# Heaters.net
KiCad netlist of a schematic drawn in Altium Designer
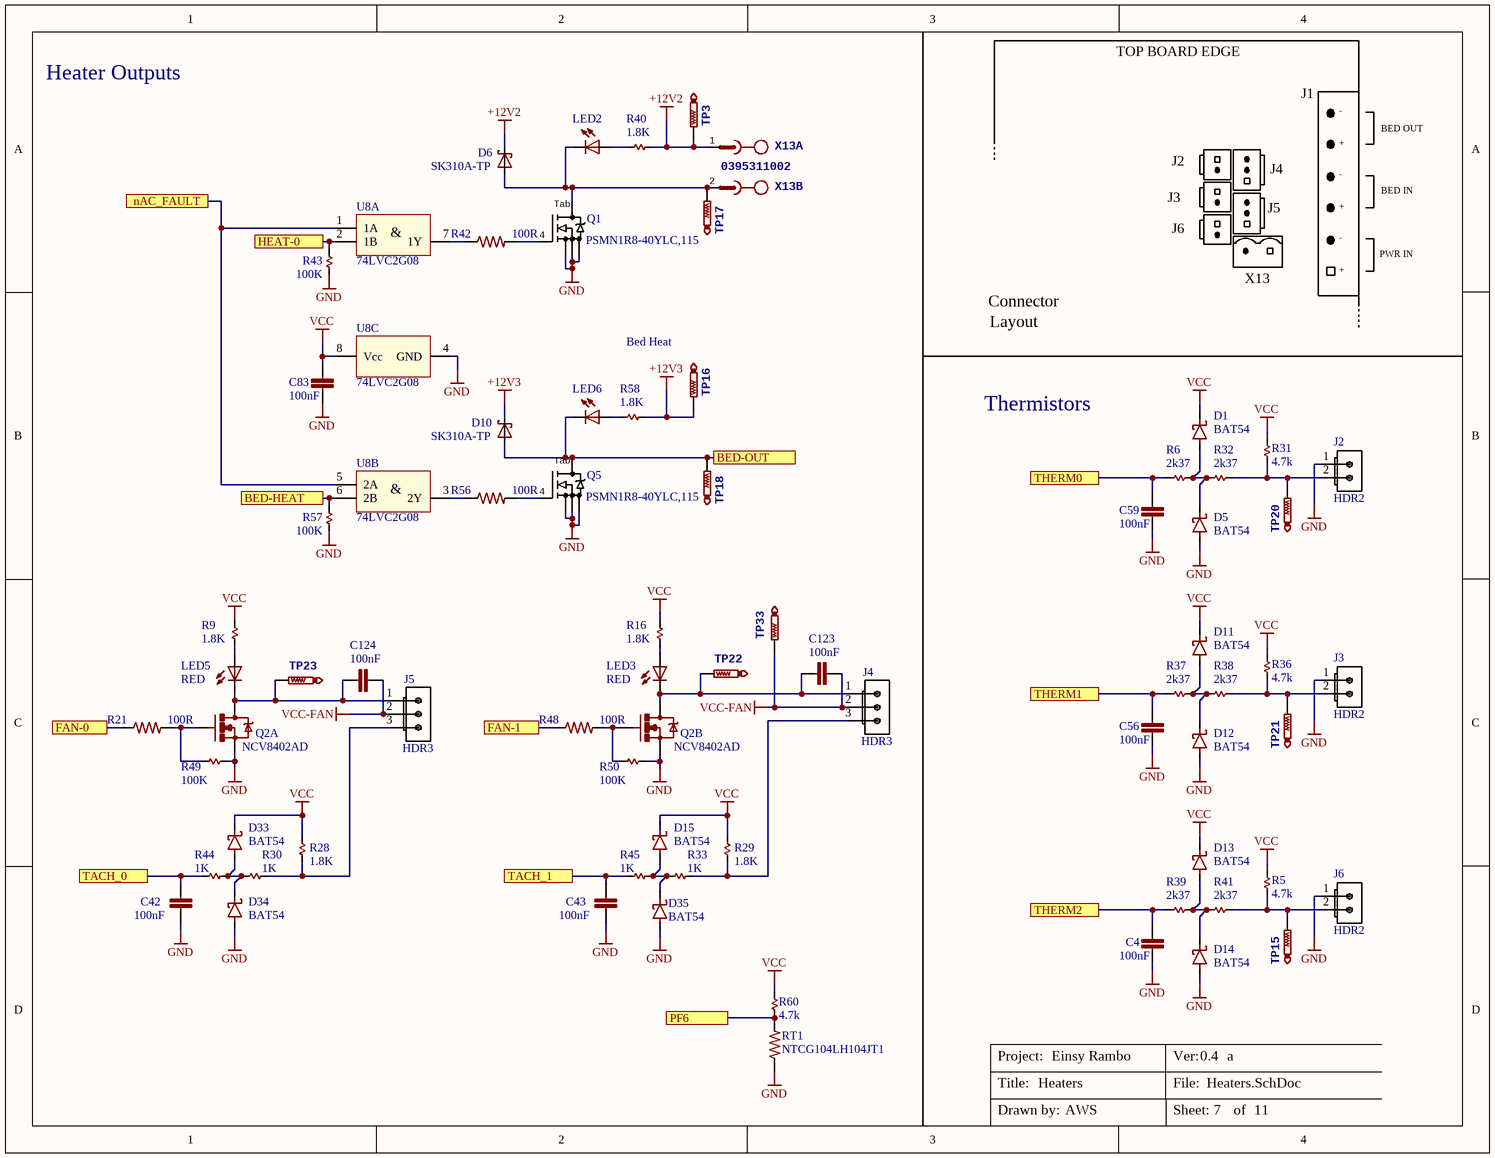
[diagram p0: Heaters.SchDoc]

(export (version "E")
  (design (tool "Eeschema 10.0.6"))
  (components
    (comp (ref "C4")
      (value "100nF")
      (footprint "C0402")
      (description "CAP CER 0402 100nF 16V 10% X7R")
      (fields (field (name "MANUFACTURER") "Murata") (field (name "TOLERANCE") "+/- 10%"))
      (libsource (lib "3Delight") (part "GRM155R71C104KA88D"))
    )
    (comp (ref "C42")
      (value "100nF")
      (footprint "C0402")
      (description "CAP CER 0402 100nF 16V 10% X7R")
      (fields (field (name "MANUFACTURER") "Murata") (field (name "TOLERANCE") "+/- 10%"))
      (libsource (lib "3Delight") (part "GRM155R71C104KA88D"))
    )
    (comp (ref "C43")
      (value "100nF")
      (footprint "C0402")
      (description "CAP CER 0402 100nF 16V 10% X7R")
      (fields (field (name "MANUFACTURER") "Murata") (field (name "TOLERANCE") "+/- 10%"))
      (libsource (lib "3Delight") (part "GRM155R71C104KA88D"))
    )
    (comp (ref "C56")
      (value "100nF")
      (footprint "C0402")
      (description "CAP CER 0402 100nF 16V 10% X7R")
      (fields (field (name "MANUFACTURER") "Murata") (field (name "TOLERANCE") "+/- 10%"))
      (libsource (lib "3Delight") (part "GRM155R71C104KA88D"))
    )
    (comp (ref "C59")
      (value "100nF")
      (footprint "C0402")
      (description "CAP CER 0402 100nF 16V 10% X7R")
      (fields (field (name "MANUFACTURER") "Murata") (field (name "TOLERANCE") "+/- 10%"))
      (libsource (lib "3Delight") (part "GRM155R71C104KA88D"))
    )
    (comp (ref "C83")
      (value "100nF")
      (footprint "C0402")
      (description "CAP CER 0402 100nF 16V 10% X7R")
      (fields (field (name "MANUFACTURER") "Murata") (field (name "TOLERANCE") "+/- 10%"))
      (libsource (lib "3Delight") (part "GRM155R71C104KA88D"))
    )
    (comp (ref "C123")
      (value "100nF")
      (footprint "C0402")
      (description "CAP CER 0402 100nF 16V 10% X7R")
      (fields (field (name "MANUFACTURER") "Murata") (field (name "TOLERANCE") "+/- 10%"))
      (libsource (lib "") (part "GRM155R71C104KA88D_1"))
    )
    (comp (ref "C124")
      (value "100nF")
      (footprint "C0402")
      (description "CAP CER 0402 100nF 16V 10% X7R")
      (fields (field (name "MANUFACTURER") "Murata") (field (name "TOLERANCE") "+/- 10%"))
      (libsource (lib "") (part "GRM155R71C104KA88D_1"))
    )
    (comp (ref "D1")
      (value "BAT54")
      (footprint "SOD523_IPC")
      (description "Diode Schottky 30V 100mA Surface Mount SOD-523")
      (fields (field (name "MANUFACTURER") "Diodes Incorporated") (field (name "TOLERANCE") "NA"))
      (libsource (lib "3Delight") (part "BAT54WT-7"))
    )
    (comp (ref "D5")
      (value "BAT54")
      (footprint "SOD523_IPC")
      (description "Diode Schottky 30V 100mA Surface Mount SOD-523")
      (fields (field (name "MANUFACTURER") "Diodes Incorporated") (field (name "TOLERANCE") "NA"))
      (libsource (lib "3Delight") (part "BAT54WT-7"))
    )
    (comp (ref "D6")
      (value "SK310A-TP")
      (footprint "SMA-SM")
      (description "DIODE Schottky 3A SMA")
      (fields (field (name "MANUFACTURER") "MCC") (field (name "PART") "SK310A"))
      (libsource (lib "3Delight") (part "SK310A"))
    )
    (comp (ref "D10")
      (value "SK310A-TP")
      (footprint "SMA-SM")
      (description "DIODE Schottky 3A SMA")
      (fields (field (name "MANUFACTURER") "MCC") (field (name "PART") "SK310A"))
      (libsource (lib "3Delight") (part "SK310A"))
    )
    (comp (ref "D11")
      (value "BAT54")
      (footprint "SOD523_IPC")
      (description "Diode Schottky 30V 100mA Surface Mount SOD-523")
      (fields (field (name "MANUFACTURER") "Diodes Incorporated") (field (name "TOLERANCE") "NA"))
      (libsource (lib "3Delight") (part "BAT54WT-7"))
    )
    (comp (ref "D12")
      (value "BAT54")
      (footprint "SOD523_IPC")
      (description "Diode Schottky 30V 100mA Surface Mount SOD-523")
      (fields (field (name "MANUFACTURER") "Diodes Incorporated") (field (name "TOLERANCE") "NA"))
      (libsource (lib "3Delight") (part "BAT54WT-7"))
    )
    (comp (ref "D13")
      (value "BAT54")
      (footprint "SOD523_IPC")
      (description "Diode Schottky 30V 100mA Surface Mount SOD-523")
      (fields (field (name "MANUFACTURER") "Diodes Incorporated") (field (name "TOLERANCE") "NA"))
      (libsource (lib "3Delight") (part "BAT54WT-7"))
    )
    (comp (ref "D14")
      (value "BAT54")
      (footprint "SOD523_IPC")
      (description "Diode Schottky 30V 100mA Surface Mount SOD-523")
      (fields (field (name "MANUFACTURER") "Diodes Incorporated") (field (name "TOLERANCE") "NA"))
      (libsource (lib "3Delight") (part "BAT54WT-7"))
    )
    (comp (ref "D15")
      (value "BAT54")
      (footprint "SOD523_IPC")
      (description "Diode Schottky 30V 100mA Surface Mount SOD-523")
      (fields (field (name "MANUFACTURER") "Diodes Incorporated") (field (name "TOLERANCE") "NA"))
      (libsource (lib "3Delight") (part "BAT54WT-7"))
    )
    (comp (ref "D33")
      (value "BAT54")
      (footprint "SOD523_IPC")
      (description "Diode Schottky 30V 100mA Surface Mount SOD-523")
      (fields (field (name "MANUFACTURER") "Diodes Incorporated") (field (name "TOLERANCE") "NA"))
      (libsource (lib "3Delight") (part "BAT54WT-7"))
    )
    (comp (ref "D34")
      (value "BAT54")
      (footprint "SOD523_IPC")
      (description "Diode Schottky 30V 100mA Surface Mount SOD-523")
      (fields (field (name "MANUFACTURER") "Diodes Incorporated") (field (name "TOLERANCE") "NA"))
      (libsource (lib "3Delight") (part "BAT54WT-7"))
    )
    (comp (ref "D35")
      (value "BAT54")
      (footprint "SOD523_IPC")
      (description "Diode Schottky 30V 100mA Surface Mount SOD-523")
      (fields (field (name "MANUFACTURER") "Diodes Incorporated") (field (name "TOLERANCE") "NA"))
      (libsource (lib "3Delight") (part "BAT54WT-7"))
    )
    (comp (ref "J2")
      (value "HDR2")
      (footprint "70543-02 PIN-IN-PASTE")
      (description "Connector 2pos")
      (fields (field (name "MANUFACTURER") "Molex") (field (name "PART") "2 Pin Conn"))
      (libsource (lib "Connectors") (part "CONN 2PIN VERT 0.1{dblquote} SHRD LOCKING PIN-IN-PASTE"))
    )
    (comp (ref "J3")
      (value "HDR2")
      (footprint "70543-02 PIN-IN-PASTE")
      (description "Connector 2pos")
      (fields (field (name "MANUFACTURER") "Molex") (field (name "PART") "2 Pin Conn"))
      (libsource (lib "Connectors") (part "CONN 2PIN VERT 0.1{dblquote} SHRD LOCKING PIN-IN-PASTE"))
    )
    (comp (ref "J4")
      (value "HDR3")
      (footprint "70543-03 PIN-IN-PASTE")
      (description "3 Positions Header, Shrouded Connector 0.100\" (2.54mm) Through Hole Gold")
      (fields (field (name "MANUFACTURER") "Molex") (field (name "PART") "3 Pin Conn VERT"))
      (libsource (lib "Connectors") (part "CONN 3POS VERT 0.1{dblquote} SHRD LOCKING PIN-IN-PASTE"))
    )
    (comp (ref "J5")
      (value "HDR3")
      (footprint "70543-03 PIN-IN-PASTE")
      (description "3 Positions Header, Shrouded Connector 0.100\" (2.54mm) Through Hole Gold")
      (fields (field (name "MANUFACTURER") "Molex") (field (name "PART") "3 Pin Conn VERT"))
      (libsource (lib "Connectors") (part "CONN 3POS VERT 0.1{dblquote} SHRD LOCKING PIN-IN-PASTE"))
    )
    (comp (ref "J6")
      (value "HDR2")
      (footprint "70543-02 PIN-IN-PASTE")
      (description "Connector 2pos")
      (fields (field (name "MANUFACTURER") "Molex") (field (name "PART") "2 Pin Conn"))
      (libsource (lib "Connectors") (part "CONN 2PIN VERT 0.1{dblquote} SHRD LOCKING PIN-IN-PASTE"))
    )
    (comp (ref "LED2")
      (value "RED")
      (footprint "LED2012120")
      (description "LED 0805 Red")
      (fields (field (name "MANUFACTURER") "Dialight") (field (name "TOLERANCE") "NA"))
      (libsource (lib "3Delight") (part "5988110107F"))
    )
    (comp (ref "LED3")
      (value "RED")
      (footprint "LED2012120")
      (description "LED 0805 Red")
      (fields
        (field (name "MANUFACTURER") "Dialight")
        (field (name "PART") "RED")
        (field (name "TOLERANCE") "NA")
      )
      (libsource (lib "3Delight") (part "5988110107F"))
    )
    (comp (ref "LED5")
      (value "RED")
      (footprint "LED2012120")
      (description "LED 0805 Red")
      (fields
        (field (name "MANUFACTURER") "Dialight")
        (field (name "PART") "RED")
        (field (name "TOLERANCE") "NA")
      )
      (libsource (lib "3Delight") (part "5988110107F"))
    )
    (comp (ref "LED6")
      (value "RED")
      (footprint "LED2012120")
      (description "LED 0805 Red")
      (fields (field (name "MANUFACTURER") "Dialight") (field (name "TOLERANCE") "NA"))
      (libsource (lib "3Delight") (part "5988110107F"))
    )
    (comp (ref "Q1")
      (value "PSMN1R8-40YLC,115")
      (footprint "SOT669_ClosedBotVias")
      (description "MOSFET N-CH 40V 100A LFPAK")
      (fields (field (name "MANUFACTURER") "Nexperia") (field (name "TOLERANCE") "-NA-"))
      (libsource (lib "Transistors") (part "PSMN1R8-40YLC_ClosedBotVias"))
    )
    (comp (ref "Q2")
      (value "NCV8402AD")
      (footprint "NCV8402AD-SOIC8")
      (description "IC DVR LOW SIDE 8-SOIC")
      (fields (field (name "MANUFACTURER") "On Semi") (field (name "PART") "NCV8402"))
      (libsource (lib "3Delight") (part "NCV8402AD"))
    )
    (comp (ref "Q5")
      (value "PSMN1R8-40YLC,115")
      (footprint "SOT669_ClosedBotVias")
      (description "MOSFET N-CH 40V 100A LFPAK")
      (fields (field (name "MANUFACTURER") "Nexperia") (field (name "TOLERANCE") "-NA-"))
      (libsource (lib "Transistors") (part "PSMN1R8-40YLC_ClosedBotVias"))
    )
    (comp (ref "R5")
      (value "4.7k")
      (footprint "R0402")
      (description "RES SMD 4.7K OHM 1% 1/16W 0402")
      (fields (field (name "MANUFACTURER") "Yageo") (field (name "TOLERANCE") "+/- 1%"))
      (libsource (lib "3Delight") (part "RC0402FR-074K7L"))
    )
    (comp (ref "R6")
      (value "2k37")
      (footprint "R0402")
      (description "RES SMD 2.37K OHM 1% 1/16W 0402")
      (fields (field (name "MANUFACTURER") "Yageo") (field (name "PART") "2.37k"))
      (libsource (lib "3Delight") (part "RC0402FR-072K37L"))
    )
    (comp (ref "R9")
      (value "1.8K")
      (footprint "R0402")
      (description "RES SMD 1.8K OHM 1% 1/16W 0402")
      (fields (field (name "MANUFACTURER") "Yageo") (field (name "PART") "1.8k"))
      (libsource (lib "3Delight") (part "RC0402FR-071K8L"))
    )
    (comp (ref "R16")
      (value "1.8K")
      (footprint "R0402")
      (description "RES SMD 1.8K OHM 1% 1/16W 0402")
      (fields (field (name "MANUFACTURER") "Yageo") (field (name "PART") "1.8k"))
      (libsource (lib "3Delight") (part "RC0402FR-071K8L"))
    )
    (comp (ref "R21")
      (value "100R")
      (footprint "R0402")
      (description "RES SMD 100 OHM 1% 1/16W 0402")
      (fields (field (name "MANUFACTURER") "Yageo") (field (name "PART") "100R 1% 0402"))
      (libsource (lib "Archim") (part "RES 100R 0402 1%"))
    )
    (comp (ref "R28")
      (value "1.8K")
      (footprint "R0402")
      (description "RES SMD 1.8K OHM 1% 1/16W 0402")
      (fields (field (name "MANUFACTURER") "Yageo") (field (name "PART") "1.8k"))
      (libsource (lib "3Delight") (part "RC0402FR-071K8L"))
    )
    (comp (ref "R29")
      (value "1.8K")
      (footprint "R0402")
      (description "RES SMD 1.8K OHM 1% 1/16W 0402")
      (fields (field (name "MANUFACTURER") "Yageo") (field (name "PART") "1.8k"))
      (libsource (lib "3Delight") (part "RC0402FR-071K8L"))
    )
    (comp (ref "R30")
      (value "1K")
      (footprint "R0402")
      (description "RES SMD 1K OHM 1% 1/16W 0402")
      (fields (field (name "MANUFACTURER") "Yageo") (field (name "PART") "1k"))
      (libsource (lib "3Delight") (part "RC0402FR-071KL"))
    )
    (comp (ref "R31")
      (value "4.7k")
      (footprint "R0402")
      (description "RES SMD 4.7K OHM 1% 1/16W 0402")
      (fields (field (name "MANUFACTURER") "Yageo") (field (name "TOLERANCE") "+/- 1%"))
      (libsource (lib "3Delight") (part "RC0402FR-074K7L"))
    )
    (comp (ref "R32")
      (value "2k37")
      (footprint "R0402")
      (description "RES SMD 2.37K OHM 1% 1/16W 0402")
      (fields (field (name "MANUFACTURER") "Yageo") (field (name "PART") "2.37k"))
      (libsource (lib "3Delight") (part "RC0402FR-072K37L"))
    )
    (comp (ref "R33")
      (value "1K")
      (footprint "R0402")
      (description "RES SMD 1K OHM 1% 1/16W 0402")
      (fields (field (name "MANUFACTURER") "Yageo") (field (name "PART") "1k"))
      (libsource (lib "3Delight") (part "RC0402FR-071KL"))
    )
    (comp (ref "R36")
      (value "4.7k")
      (footprint "R0402")
      (description "RES SMD 4.7K OHM 1% 1/16W 0402")
      (fields (field (name "MANUFACTURER") "Yageo") (field (name "TOLERANCE") "+/- 1%"))
      (libsource (lib "3Delight") (part "RC0402FR-074K7L"))
    )
    (comp (ref "R37")
      (value "2k37")
      (footprint "R0402")
      (description "RES SMD 2.37K OHM 1% 1/16W 0402")
      (fields (field (name "MANUFACTURER") "Yageo") (field (name "PART") "2.37k"))
      (libsource (lib "3Delight") (part "RC0402FR-072K37L"))
    )
    (comp (ref "R38")
      (value "2k37")
      (footprint "R0402")
      (description "RES SMD 2.37K OHM 1% 1/16W 0402")
      (fields (field (name "MANUFACTURER") "Yageo") (field (name "PART") "2.37k"))
      (libsource (lib "3Delight") (part "RC0402FR-072K37L"))
    )
    (comp (ref "R39")
      (value "2k37")
      (footprint "R0402")
      (description "RES SMD 2.37K OHM 1% 1/16W 0402")
      (fields (field (name "MANUFACTURER") "Yageo") (field (name "PART") "2.37k"))
      (libsource (lib "3Delight") (part "RC0402FR-072K37L"))
    )
    (comp (ref "R40")
      (value "1.8K")
      (footprint "R0402")
      (description "RES SMD 1.8K OHM 1% 1/16W 0402")
      (fields (field (name "MANUFACTURER") "Yageo") (field (name "PART") "1.8k"))
      (libsource (lib "3Delight") (part "RC0402FR-071K8L"))
    )
    (comp (ref "R41")
      (value "2k37")
      (footprint "R0402")
      (description "RES SMD 2.37K OHM 1% 1/16W 0402")
      (fields (field (name "MANUFACTURER") "Yageo") (field (name "PART") "2.37k"))
      (libsource (lib "3Delight") (part "RC0402FR-072K37L"))
    )
    (comp (ref "R42")
      (value "100R")
      (footprint "R0402")
      (description "RES SMD 100 OHM 1% 1/16W 0402")
      (fields (field (name "MANUFACTURER") "Yageo") (field (name "PART") "100R 1% 0402"))
      (libsource (lib "Archim") (part "RES 100R 0402 1%"))
    )
    (comp (ref "R43")
      (value "100K")
      (footprint "R0402")
      (description "RES 100K OHM 1% 1/16W 0402")
      (fields (field (name "MANUFACTURER") "Yageo") (field (name "TOLERANCE") "+/- 1%"))
      (libsource (lib "3Delight") (part "RC0402FR-07100KL"))
    )
    (comp (ref "R44")
      (value "1K")
      (footprint "R0402")
      (description "RES SMD 1K OHM 1% 1/16W 0402")
      (fields (field (name "MANUFACTURER") "Yageo") (field (name "PART") "1k"))
      (libsource (lib "3Delight") (part "RC0402FR-071KL"))
    )
    (comp (ref "R45")
      (value "1K")
      (footprint "R0402")
      (description "RES SMD 1K OHM 1% 1/16W 0402")
      (fields (field (name "MANUFACTURER") "Yageo") (field (name "PART") "1k"))
      (libsource (lib "3Delight") (part "RC0402FR-071KL"))
    )
    (comp (ref "R48")
      (value "100R")
      (footprint "R0402")
      (description "RES SMD 100 OHM 1% 1/16W 0402")
      (fields (field (name "MANUFACTURER") "Yageo") (field (name "PART") "100R 1% 0402"))
      (libsource (lib "Archim") (part "RES 100R 0402 1%"))
    )
    (comp (ref "R49")
      (value "100K")
      (footprint "R0402")
      (description "RES 100K OHM 1% 1/16W 0402")
      (fields (field (name "MANUFACTURER") "Yageo") (field (name "TOLERANCE") "+/- 1%"))
      (libsource (lib "3Delight") (part "RC0402FR-07100KL"))
    )
    (comp (ref "R50")
      (value "100K")
      (footprint "R0402")
      (description "RES 100K OHM 1% 1/16W 0402")
      (fields (field (name "MANUFACTURER") "Yageo") (field (name "TOLERANCE") "+/- 1%"))
      (libsource (lib "3Delight") (part "RC0402FR-07100KL"))
    )
    (comp (ref "R56")
      (value "100R")
      (footprint "R0402")
      (description "RES SMD 100 OHM 1% 1/16W 0402")
      (fields (field (name "MANUFACTURER") "Yageo") (field (name "PART") "100R 1% 0402"))
      (libsource (lib "Archim") (part "RES 100R 0402 1%"))
    )
    (comp (ref "R57")
      (value "100K")
      (footprint "R0402")
      (description "RES 100K OHM 1% 1/16W 0402")
      (fields (field (name "MANUFACTURER") "Yageo") (field (name "TOLERANCE") "+/- 1%"))
      (libsource (lib "3Delight") (part "RC0402FR-07100KL"))
    )
    (comp (ref "R58")
      (value "1.8K")
      (footprint "R0402")
      (description "RES SMD 1.8K OHM 1% 1/16W 0402")
      (fields (field (name "MANUFACTURER") "Yageo") (field (name "PART") "1.8k"))
      (libsource (lib "3Delight") (part "RC0402FR-071K8L"))
    )
    (comp (ref "R60")
      (value "4.7k")
      (footprint "R0402")
      (description "RES SMD 4.7K OHM 1% 1/16W 0402")
      (fields (field (name "MANUFACTURER") "Yageo") (field (name "TOLERANCE") "+/- 1%"))
      (libsource (lib "3Delight") (part "RC0402FR-074K7L"))
    )
    (comp (ref "RT1")
      (value "NTCG104LH104JT1")
      (footprint "R0402")
      (description "Resistor")
      (fields (field (name "PUBLISHER") "UltiMachine"))
      (libsource (lib "3Delight") (part "R0402TBD"))
    )
    (comp (ref "TP3")
      (value "TestPoint")
      (footprint "TP1-27")
      (description "Test Point")
      (libsource (lib "") (part "TestPoint_2"))
    )
    (comp (ref "TP15")
      (value "TestPoint")
      (footprint "TP1-27")
      (description "Test Point")
      (libsource (lib "") (part "TestPoint_1"))
    )
    (comp (ref "TP16")
      (value "TestPoint")
      (footprint "TP1-27")
      (description "Test Point")
      (libsource (lib "") (part "TestPoint_2"))
    )
    (comp (ref "TP17")
      (value "TestPoint")
      (footprint "TP1-27")
      (description "Test Point")
      (libsource (lib "") (part "TestPoint_1"))
    )
    (comp (ref "TP18")
      (value "TestPoint")
      (footprint "TP1-27")
      (description "Test Point")
      (libsource (lib "") (part "TestPoint_1"))
    )
    (comp (ref "TP20")
      (value "TestPoint")
      (footprint "TP1-27")
      (description "Test Point")
      (libsource (lib "") (part "TestPoint_1"))
    )
    (comp (ref "TP21")
      (value "TestPoint")
      (footprint "TP1-27")
      (description "Test Point")
      (libsource (lib "") (part "TestPoint_1"))
    )
    (comp (ref "TP22")
      (value "TestPoint")
      (footprint "TP1-27")
      (description "Test Point")
      (libsource (lib "3Delight") (part "TestPoint"))
    )
    (comp (ref "TP23")
      (value "TestPoint")
      (footprint "TP1-27")
      (description "Test Point")
      (libsource (lib "3Delight") (part "TestPoint"))
    )
    (comp (ref "TP33")
      (value "TestPoint")
      (footprint "TP1-27")
      (description "Test Point")
      (libsource (lib "") (part "TestPoint_2"))
    )
    (comp (ref "U8")
      (value "74LVC2G08")
      (footprint "VSSOP8")
      (description "IC GATE AND 2CH 2-INP 8-VSSOP")
      (fields (field (name "TOLERANCE") "-NA-") (field (name "MANUFACTURER") "Nexperia"))
      (libsource (lib "ICs-Logic") (part "74LVC2G08"))
    )
    (comp (ref "X13")
      (value "0395311002")
      (footprint "MSTBV2")
      (description "Conn - 5.08mm Pitch Fixed")
      (fields (field (name "MANUFACTURER") "Molex") (field (name "PART") "2POS"))
      (libsource (lib "") (part "0395311002_1"))
    )
  )
  (nets
    (net (code "1") (name "+12V2") (class "Default")
      (node (ref "D6") (pin "C") (pinfunction "C_C") (pintype "passive"))
      (node (ref "R40") (pin "1") (pinfunction "1_1") (pintype "passive"))
      (node (ref "TP3") (pin "TP") (pinfunction "TP_TP") (pintype "passive"))
      (node (ref "X13") (pin "1") (pinfunction "1_1") (pintype "passive"))
    )
    (net (code "2") (name "+12V3") (class "Default")
      (node (ref "D10") (pin "C") (pinfunction "C_C") (pintype "passive"))
      (node (ref "R58") (pin "1") (pinfunction "1_1") (pintype "passive"))
      (node (ref "TP16") (pin "TP") (pinfunction "TP_TP") (pintype "passive"))
    )
    (net (code "3") (name "/BED-HEAT") (class "Default")
      (node (ref "R57") (pin "2") (pinfunction "2_2") (pintype "passive"))
      (node (ref "U8") (pin "6") (pinfunction "2B_6") (pintype "passive"))
    )
    (net (code "4") (name "/BED-OUT") (class "Default")
      (node (ref "D10") (pin "A") (pinfunction "A_A") (pintype "passive"))
      (node (ref "LED6") (pin "C") (pinfunction "C_C") (pintype "passive"))
      (node (ref "Q5") (pin "TAB") (pinfunction "D_TAB") (pintype "passive"))
      (node (ref "TP18") (pin "TP") (pinfunction "TP_TP") (pintype "passive"))
    )
    (net (code "5") (name "/FAN-0") (class "Default")
      (node (ref "R21") (pin "1") (pinfunction "1_1") (pintype "passive"))
    )
    (net (code "6") (name "/FAN-1") (class "Default")
      (node (ref "R48") (pin "1") (pinfunction "1_1") (pintype "passive"))
    )
    (net (code "7") (name "/HEAT-0") (class "Default")
      (node (ref "R43") (pin "2") (pinfunction "2_2") (pintype "passive"))
      (node (ref "U8") (pin "2") (pinfunction "1B_2") (pintype "passive"))
    )
    (net (code "8") (name "/PF6") (class "Default")
      (node (ref "R60") (pin "1") (pinfunction "1_1") (pintype "passive"))
      (node (ref "RT1") (pin "2") (pinfunction "2_2") (pintype "passive"))
    )
    (net (code "9") (name "/TACH_0") (class "Default")
      (node (ref "C42") (pin "1") (pinfunction "1_1") (pintype "passive"))
      (node (ref "R44") (pin "1") (pinfunction "1_1") (pintype "passive"))
    )
    (net (code "10") (name "/TACH_1") (class "Default")
      (node (ref "C43") (pin "1") (pinfunction "1_1") (pintype "passive"))
      (node (ref "R45") (pin "1") (pinfunction "1_1") (pintype "passive"))
    )
    (net (code "11") (name "/THERM0") (class "Default")
      (node (ref "C59") (pin "1") (pinfunction "1_1") (pintype "passive"))
      (node (ref "R6") (pin "2") (pinfunction "2_2") (pintype "passive"))
    )
    (net (code "12") (name "/THERM1") (class "Default")
      (node (ref "C56") (pin "1") (pinfunction "1_1") (pintype "passive"))
      (node (ref "R37") (pin "2") (pinfunction "2_2") (pintype "passive"))
    )
    (net (code "13") (name "/THERM2") (class "Default")
      (node (ref "C4") (pin "1") (pinfunction "1_1") (pintype "passive"))
      (node (ref "R39") (pin "2") (pinfunction "2_2") (pintype "passive"))
    )
    (net (code "14") (name "/nAC_FAULT") (class "Default")
      (node (ref "U8") (pin "1") (pinfunction "1A_1") (pintype "passive"))
      (node (ref "U8") (pin "5") (pinfunction "2A_5") (pintype "passive"))
    )
    (net (code "15") (name "GND") (class "Default")
      (node (ref "C4") (pin "2") (pinfunction "2_2") (pintype "passive"))
      (node (ref "C42") (pin "2") (pinfunction "2_2") (pintype "passive"))
      (node (ref "C43") (pin "2") (pinfunction "2_2") (pintype "passive"))
      (node (ref "C56") (pin "2") (pinfunction "2_2") (pintype "passive"))
      (node (ref "C59") (pin "2") (pinfunction "2_2") (pintype "passive"))
      (node (ref "C83") (pin "2") (pinfunction "2_2") (pintype "passive"))
      (node (ref "D12") (pin "A") (pinfunction "A_A") (pintype "passive"))
      (node (ref "D14") (pin "A") (pinfunction "A_A") (pintype "passive"))
      (node (ref "D34") (pin "A") (pinfunction "A_A") (pintype "passive"))
      (node (ref "D35") (pin "A") (pinfunction "A_A") (pintype "passive"))
      (node (ref "D5") (pin "A") (pinfunction "A_A") (pintype "passive"))
      (node (ref "J2") (pin "1") (pinfunction "S_1") (pintype "passive"))
      (node (ref "J3") (pin "1") (pinfunction "S_1") (pintype "passive"))
      (node (ref "J6") (pin "1") (pinfunction "S_1") (pintype "passive"))
      (node (ref "Q1") (pin "1") (pinfunction "S_1") (pintype "passive"))
      (node (ref "Q1") (pin "2") (pinfunction "S_2") (pintype "passive"))
      (node (ref "Q1") (pin "3") (pinfunction "S_3") (pintype "passive"))
      (node (ref "Q2") (pin "1") (pinfunction "S_1") (pintype "passive"))
      (node (ref "Q2") (pin "3") (pinfunction "S_3") (pintype "passive"))
      (node (ref "Q5") (pin "1") (pinfunction "S_1") (pintype "passive"))
      (node (ref "Q5") (pin "2") (pinfunction "S_2") (pintype "passive"))
      (node (ref "Q5") (pin "3") (pinfunction "S_3") (pintype "passive"))
      (node (ref "R43") (pin "1") (pinfunction "1_1") (pintype "passive"))
      (node (ref "R49") (pin "2") (pinfunction "2_2") (pintype "passive"))
      (node (ref "R50") (pin "2") (pinfunction "2_2") (pintype "passive"))
      (node (ref "R57") (pin "1") (pinfunction "1_1") (pintype "passive"))
      (node (ref "RT1") (pin "1") (pinfunction "1_1") (pintype "passive"))
      (node (ref "U8") (pin "4") (pinfunction "GND_4") (pintype "passive"))
    )
    (net (code "16") (name "Net-(D1-PadA)") (class "Default")
      (node (ref "D1") (pin "A") (pinfunction "A_A") (pintype "passive"))
      (node (ref "D5") (pin "K") (pinfunction "K_K") (pintype "passive"))
      (node (ref "R32") (pin "2") (pinfunction "2_2") (pintype "passive"))
      (node (ref "R6") (pin "1") (pinfunction "1_1") (pintype "passive"))
    )
    (net (code "17") (name "Net-(D11-PadA)") (class "Default")
      (node (ref "D11") (pin "A") (pinfunction "A_A") (pintype "passive"))
      (node (ref "D12") (pin "K") (pinfunction "K_K") (pintype "passive"))
      (node (ref "R37") (pin "1") (pinfunction "1_1") (pintype "passive"))
      (node (ref "R38") (pin "2") (pinfunction "2_2") (pintype "passive"))
    )
    (net (code "18") (name "Net-(D13-PadA)") (class "Default")
      (node (ref "D13") (pin "A") (pinfunction "A_A") (pintype "passive"))
      (node (ref "D14") (pin "K") (pinfunction "K_K") (pintype "passive"))
      (node (ref "R39") (pin "1") (pinfunction "1_1") (pintype "passive"))
      (node (ref "R41") (pin "2") (pinfunction "2_2") (pintype "passive"))
    )
    (net (code "19") (name "Net-(D15-PadA)") (class "Default")
      (node (ref "D15") (pin "A") (pinfunction "A_A") (pintype "passive"))
      (node (ref "D35") (pin "K") (pinfunction "K_K") (pintype "passive"))
      (node (ref "R33") (pin "1") (pinfunction "1_1") (pintype "passive"))
      (node (ref "R45") (pin "2") (pinfunction "2_2") (pintype "passive"))
    )
    (net (code "20") (name "Net-(D33-PadA)") (class "Default")
      (node (ref "D33") (pin "A") (pinfunction "A_A") (pintype "passive"))
      (node (ref "D34") (pin "K") (pinfunction "K_K") (pintype "passive"))
      (node (ref "R30") (pin "1") (pinfunction "1_1") (pintype "passive"))
      (node (ref "R44") (pin "2") (pinfunction "2_2") (pintype "passive"))
    )
    (net (code "21") (name "Net-(J2-S-Pad2)") (class "Default")
      (node (ref "J2") (pin "2") (pinfunction "S_2") (pintype "passive"))
      (node (ref "R31") (pin "1") (pinfunction "1_1") (pintype "passive"))
      (node (ref "R32") (pin "1") (pinfunction "1_1") (pintype "passive"))
      (node (ref "TP20") (pin "TP") (pinfunction "TP_TP") (pintype "passive"))
    )
    (net (code "22") (name "Net-(J3-S-Pad2)") (class "Default")
      (node (ref "J3") (pin "2") (pinfunction "S_2") (pintype "passive"))
      (node (ref "R36") (pin "1") (pinfunction "1_1") (pintype "passive"))
      (node (ref "R38") (pin "1") (pinfunction "1_1") (pintype "passive"))
      (node (ref "TP21") (pin "TP") (pinfunction "TP_TP") (pintype "passive"))
    )
    (net (code "23") (name "Net-(J4-S-Pad3)") (class "Default")
      (node (ref "J4") (pin "3") (pinfunction "S_3") (pintype "passive"))
      (node (ref "R29") (pin "1") (pinfunction "1_1") (pintype "passive"))
      (node (ref "R33") (pin "2") (pinfunction "2_2") (pintype "passive"))
    )
    (net (code "24") (name "Net-(J5-S-Pad3)") (class "Default")
      (node (ref "J5") (pin "3") (pinfunction "S_3") (pintype "passive"))
      (node (ref "R28") (pin "1") (pinfunction "1_1") (pintype "passive"))
      (node (ref "R30") (pin "2") (pinfunction "2_2") (pintype "passive"))
    )
    (net (code "25") (name "Net-(J6-S-Pad2)") (class "Default")
      (node (ref "J6") (pin "2") (pinfunction "S_2") (pintype "passive"))
      (node (ref "R41") (pin "1") (pinfunction "1_1") (pintype "passive"))
      (node (ref "R5") (pin "1") (pinfunction "1_1") (pintype "passive"))
      (node (ref "TP15") (pin "TP") (pinfunction "TP_TP") (pintype "passive"))
    )
    (net (code "26") (name "Net-(LED2-PadA)") (class "Default")
      (node (ref "LED2") (pin "A") (pinfunction "A_A") (pintype "passive"))
      (node (ref "R40") (pin "2") (pinfunction "2_2") (pintype "passive"))
    )
    (net (code "27") (name "Net-(LED3-PadA)") (class "Default")
      (node (ref "LED3") (pin "A") (pinfunction "A_A") (pintype "passive"))
      (node (ref "R16") (pin "2") (pinfunction "2_2") (pintype "passive"))
    )
    (net (code "28") (name "Net-(LED5-PadA)") (class "Default")
      (node (ref "LED5") (pin "A") (pinfunction "A_A") (pintype "passive"))
      (node (ref "R9") (pin "2") (pinfunction "2_2") (pintype "passive"))
    )
    (net (code "29") (name "Net-(LED6-PadA)") (class "Default")
      (node (ref "LED6") (pin "A") (pinfunction "A_A") (pintype "passive"))
      (node (ref "R58") (pin "2") (pinfunction "2_2") (pintype "passive"))
    )
    (net (code "30") (name "Net-(Q1-D)") (class "Default")
      (node (ref "D6") (pin "A") (pinfunction "A_A") (pintype "passive"))
      (node (ref "LED2") (pin "C") (pinfunction "C_C") (pintype "passive"))
      (node (ref "Q1") (pin "TAB") (pinfunction "D_TAB") (pintype "passive"))
      (node (ref "TP17") (pin "TP") (pinfunction "TP_TP") (pintype "passive"))
      (node (ref "X13") (pin "2") (pinfunction "1_2") (pintype "passive"))
    )
    (net (code "31") (name "Net-(Q1-G)") (class "Default")
      (node (ref "Q1") (pin "4") (pinfunction "G_4") (pintype "passive"))
      (node (ref "R42") (pin "2") (pinfunction "2_2") (pintype "passive"))
    )
    (net (code "32") (name "Net-(Q2A-D)") (class "Default")
      (node (ref "C124") (pin "1") (pinfunction "1_1") (pintype "passive"))
      (node (ref "J5") (pin "1") (pinfunction "S_1") (pintype "passive"))
      (node (ref "LED5") (pin "C") (pinfunction "C_C") (pintype "passive"))
      (node (ref "Q2") (pin "7") (pinfunction "D_7") (pintype "passive"))
      (node (ref "TP23") (pin "TP") (pinfunction "TP_TP") (pintype "passive"))
    )
    (net (code "33") (name "Net-(Q2A-G)") (class "Default")
      (node (ref "Q2") (pin "2") (pinfunction "G_2") (pintype "passive"))
      (node (ref "R21") (pin "2") (pinfunction "2_2") (pintype "passive"))
      (node (ref "R49") (pin "1") (pinfunction "1_1") (pintype "passive"))
    )
    (net (code "34") (name "Net-(Q2B-D)") (class "Default")
      (node (ref "C123") (pin "1") (pinfunction "1_1") (pintype "passive"))
      (node (ref "J4") (pin "1") (pinfunction "S_1") (pintype "passive"))
      (node (ref "LED3") (pin "C") (pinfunction "C_C") (pintype "passive"))
      (node (ref "Q2") (pin "5") (pinfunction "D_5") (pintype "passive"))
      (node (ref "TP22") (pin "TP") (pinfunction "TP_TP") (pintype "passive"))
    )
    (net (code "35") (name "Net-(Q2B-G)") (class "Default")
      (node (ref "Q2") (pin "4") (pinfunction "G_4") (pintype "passive"))
      (node (ref "R48") (pin "2") (pinfunction "2_2") (pintype "passive"))
      (node (ref "R50") (pin "1") (pinfunction "1_1") (pintype "passive"))
    )
    (net (code "36") (name "Net-(Q5-G)") (class "Default")
      (node (ref "Q5") (pin "4") (pinfunction "G_4") (pintype "passive"))
      (node (ref "R56") (pin "2") (pinfunction "2_2") (pintype "passive"))
    )
    (net (code "37") (name "Net-(U8A-1Y)") (class "Default")
      (node (ref "R42") (pin "1") (pinfunction "1_1") (pintype "passive"))
      (node (ref "U8") (pin "7") (pinfunction "1Y_7") (pintype "passive"))
    )
    (net (code "38") (name "Net-(U8B-2Y)") (class "Default")
      (node (ref "R56") (pin "1") (pinfunction "1_1") (pintype "passive"))
      (node (ref "U8") (pin "3") (pinfunction "2Y_3") (pintype "passive"))
    )
    (net (code "39") (name "VCC") (class "Default")
      (node (ref "C83") (pin "1") (pinfunction "1_1") (pintype "passive"))
      (node (ref "D1") (pin "K") (pinfunction "K_K") (pintype "passive"))
      (node (ref "D11") (pin "K") (pinfunction "K_K") (pintype "passive"))
      (node (ref "D13") (pin "K") (pinfunction "K_K") (pintype "passive"))
      (node (ref "D15") (pin "K") (pinfunction "K_K") (pintype "passive"))
      (node (ref "D33") (pin "K") (pinfunction "K_K") (pintype "passive"))
      (node (ref "R16") (pin "1") (pinfunction "1_1") (pintype "passive"))
      (node (ref "R28") (pin "2") (pinfunction "2_2") (pintype "passive"))
      (node (ref "R29") (pin "2") (pinfunction "2_2") (pintype "passive"))
      (node (ref "R31") (pin "2") (pinfunction "2_2") (pintype "passive"))
      (node (ref "R36") (pin "2") (pinfunction "2_2") (pintype "passive"))
      (node (ref "R5") (pin "2") (pinfunction "2_2") (pintype "passive"))
      (node (ref "R60") (pin "2") (pinfunction "2_2") (pintype "passive"))
      (node (ref "R9") (pin "1") (pinfunction "1_1") (pintype "passive"))
      (node (ref "U8") (pin "8") (pinfunction "Vcc_8") (pintype "passive"))
    )
    (net (code "40") (name "VCC-FAN") (class "Default")
      (node (ref "C123") (pin "2") (pinfunction "2_2") (pintype "passive"))
      (node (ref "C124") (pin "2") (pinfunction "2_2") (pintype "passive"))
      (node (ref "J4") (pin "2") (pinfunction "S_2") (pintype "passive"))
      (node (ref "J5") (pin "2") (pinfunction "S_2") (pintype "passive"))
      (node (ref "TP33") (pin "TP") (pinfunction "TP_TP") (pintype "passive"))
    )
    (net (code "41") (name "unconnected-(U8A-NC-Pad23)") (class "Default")
      (node (ref "U8") (pin "23") (pinfunction "NC_23") (pintype "passive"))
    )
  )
)
